# CAN.net
KiCad netlist of a schematic drawn in Altium Designer
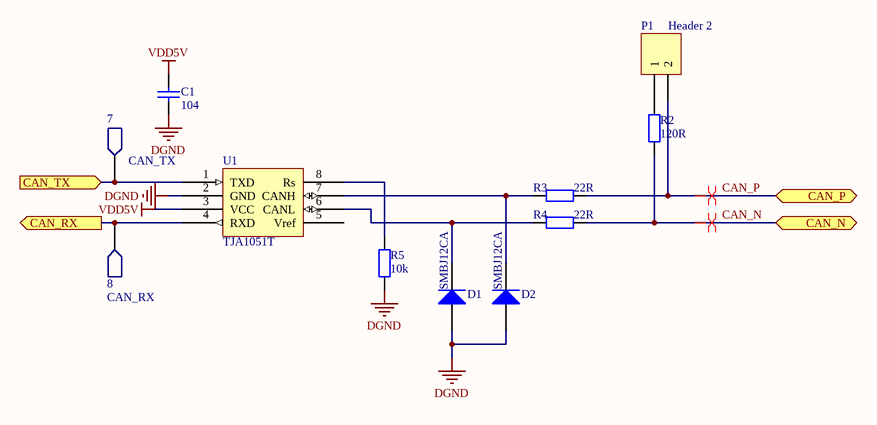
[diagram p0: CAN.SchDoc]

(export (version "E")
  (design (tool "Eeschema 10.0.6"))
  (components
    (comp (ref "7") (value "CAN_TX") (footprint "testPoint") (libsource (lib "chxxlib") (part "pad")))
    (comp (ref "8") (value "CAN_RX") (footprint "testPoint") (libsource (lib "chxxlib") (part "pad")))
    (comp (ref "C1") (value "104") (footprint "0603_") (libsource (lib "chxxlib") (part "cap")))
    (comp (ref "D1") (value "SMBJ12CA") (footprint "SMB") (libsource (lib "chxxlib") (part "diode")))
    (comp (ref "D2") (value "SMBJ12CA") (footprint "SMB") (libsource (lib "chxxlib") (part "diode")))
    (comp (ref "P1")
      (value "Header 2")
      (footprint "HDR1X2")
      (description "Header, 2-Pin")
      (fields (field (name "PUBLISHER") "Altium Limited"))
      (libsource (lib "Miscellaneous Connectors") (part "Header 2"))
    )
    (comp (ref "R2") (value "120R") (footprint "0603_") (libsource (lib "chxxlib") (part "res")))
    (comp (ref "R3") (value "22R") (footprint "0603_") (libsource (lib "") (part "res_1")))
    (comp (ref "R4") (value "22R") (footprint "0603_") (libsource (lib "") (part "res_1")))
    (comp (ref "R5") (value "10k") (footprint "0603_") (libsource (lib "chxxlib") (part "res")))
    (comp (ref "U1") (value "TJA1051T") (footprint "SOP8") (libsource (lib "chxxlib") (part "PCA82C250Y")))
  )
  (nets
    (net (code "1") (name "/CAN_N") (class "Default")
      (node (ref "R2") (pin "1") (pinfunction "1_1") (pintype "passive"))
      (node (ref "R4") (pin "1") (pinfunction "1_1") (pintype "passive"))
    )
    (net (code "2") (name "/CAN_P") (class "Default")
      (node (ref "P1") (pin "2") (pinfunction "2_2") (pintype "passive"))
      (node (ref "R3") (pin "1") (pinfunction "1_1") (pintype "passive"))
    )
    (net (code "3") (name "/CAN_RX") (class "Default")
      (node (ref "8") (pin "1") (pinfunction "1_1") (pintype "passive"))
      (node (ref "U1") (pin "4") (pinfunction "RXD_4") (pintype "output"))
    )
    (net (code "4") (name "/CAN_TX") (class "Default")
      (node (ref "7") (pin "1") (pinfunction "1_1") (pintype "passive"))
      (node (ref "U1") (pin "1") (pinfunction "TXD_1") (pintype "input"))
    )
    (net (code "5") (name "DGND") (class "Default")
      (node (ref "C1") (pin "1") (pinfunction "1_1") (pintype "passive"))
      (node (ref "D1") (pin "A") (pinfunction "A_A") (pintype "passive"))
      (node (ref "D2") (pin "A") (pinfunction "A_A") (pintype "passive"))
      (node (ref "R5") (pin "1") (pinfunction "1_1") (pintype "passive"))
      (node (ref "U1") (pin "2") (pinfunction "GND_2") (pintype "power_in"))
    )
    (net (code "6") (name "Net-(P1-Pad1)") (class "Default")
      (node (ref "P1") (pin "1") (pinfunction "1_1") (pintype "passive"))
      (node (ref "R2") (pin "2") (pinfunction "2_2") (pintype "passive"))
    )
    (net (code "7") (name "Net-(U1-CANH)") (class "Default")
      (node (ref "D2") (pin "K") (pinfunction "K_K") (pintype "passive"))
      (node (ref "R3") (pin "2") (pinfunction "2_2") (pintype "passive"))
      (node (ref "U1") (pin "7") (pinfunction "CANH_7") (pintype "bidirectional"))
    )
    (net (code "8") (name "Net-(U1-CANL)") (class "Default")
      (node (ref "D1") (pin "K") (pinfunction "K_K") (pintype "passive"))
      (node (ref "R4") (pin "2") (pinfunction "2_2") (pintype "passive"))
      (node (ref "U1") (pin "6") (pinfunction "CANL_6") (pintype "bidirectional"))
    )
    (net (code "9") (name "Net-(U1-Rs)") (class "Default")
      (node (ref "R5") (pin "2") (pinfunction "2_2") (pintype "passive"))
      (node (ref "U1") (pin "8") (pinfunction "Rs_8") (pintype "passive"))
    )
    (net (code "10") (name "VDD5V") (class "Default")
      (node (ref "C1") (pin "2") (pinfunction "2_2") (pintype "passive"))
      (node (ref "U1") (pin "3") (pinfunction "VCC_3") (pintype "power_in"))
    )
    (net (code "11") (name "unconnected-(U1-Vref-Pad5)") (class "Default")
      (node (ref "U1") (pin "5") (pinfunction "Vref_5") (pintype "passive"))
    )
  )
)
